# PowerSup.net
KiCad netlist of a schematic drawn in Altium Designer
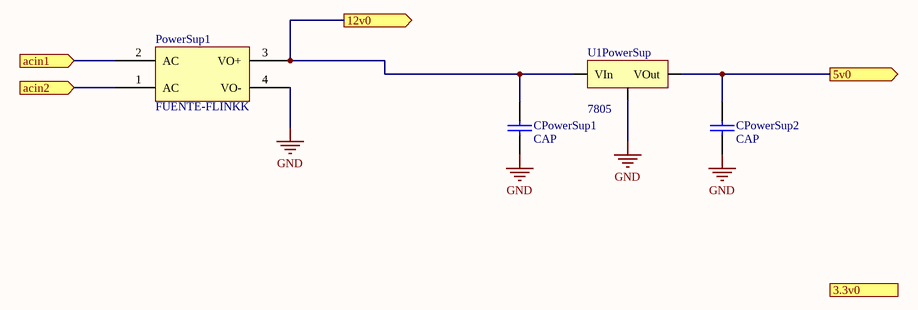
[diagram p0: PowerSup.SchDoc]

(export (version "E")
  (design (tool "Eeschema 10.0.6"))
  (components
    (comp (ref "CPowerSup1") (value "CAP") (footprint "CAP200") (libsource (lib "LIBEBAL") (part "CAP")))
    (comp (ref "CPowerSup2") (value "CAP") (footprint "CAP200") (libsource (lib "LIBEBAL") (part "CAP")))
    (comp (ref "PowerSup1")
      (value "FUENTE-FLINKK")
      (footprint "ComponentesVarios:FUENTE-HLINK")
      (libsource (lib "ComponentesVarios") (part "FUENTE-FLINKK"))
    )
    (comp (ref "U1PowerSup")
      (value "7805")
      (footprint "TO-220 H - DISIPADOR")
      (description "REGULDOR POSITIVO")
      (libsource (lib "LIBEBAL") (part "78XX"))
    )
  )
  (nets
    (net (code "2") (name "/5v0") (class "Default")
      (node (ref "CPowerSup2") (pin "1") (pinfunction "1_1") (pintype "passive"))
      (node (ref "U1PowerSup") (pin "3") (pinfunction "VOut_3") (pintype "passive"))
    )
    (net (code "3") (name "/12v0") (class "Default")
      (node (ref "CPowerSup1") (pin "1") (pinfunction "1_1") (pintype "passive"))
      (node (ref "PowerSup1") (pin "3") (pinfunction "VO+_3") (pintype "passive"))
      (node (ref "U1PowerSup") (pin "1") (pinfunction "VIn_1") (pintype "passive"))
    )
    (net (code "4") (name "/acin1") (class "Default")
      (node (ref "PowerSup1") (pin "2") (pinfunction "AC_2") (pintype "passive"))
    )
    (net (code "5") (name "/acin2") (class "Default")
      (node (ref "PowerSup1") (pin "1") (pinfunction "AC_1") (pintype "passive"))
    )
    (net (code "6") (name "GND") (class "Default")
      (node (ref "CPowerSup1") (pin "2") (pinfunction "2_2") (pintype "passive"))
      (node (ref "CPowerSup2") (pin "2") (pinfunction "2_2") (pintype "passive"))
      (node (ref "PowerSup1") (pin "4") (pinfunction "VO-_4") (pintype "passive"))
      (node (ref "U1PowerSup") (pin "2") (pinfunction "GND_2") (pintype "passive"))
    )
  )
)
